# HC06_Schem.net
KiCad netlist of a schematic drawn in Altium Designer
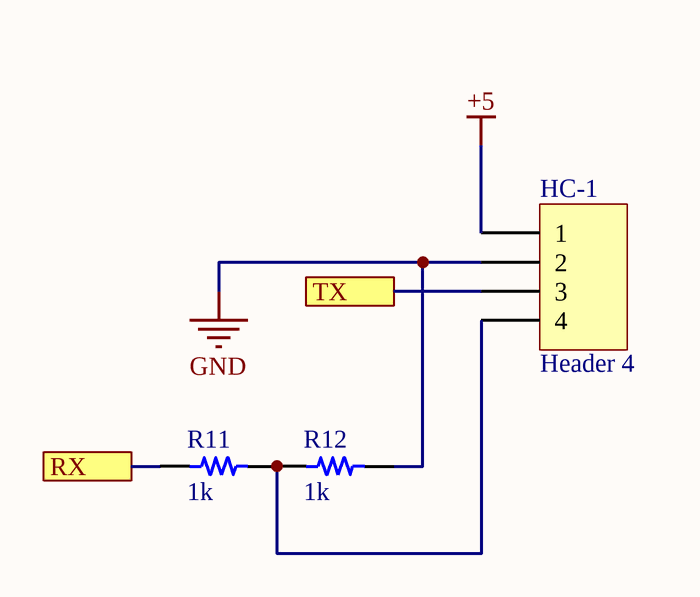
[diagram p0: HC06_Schem.SchDoc]

(export (version "E")
  (design (tool "Eeschema 10.0.6"))
  (components
    (comp (ref "HC-1")
      (value "Header 4")
      (footprint "HDR1X4")
      (description "Header, 4-Pin")
      (fields (field (name "PUBLISHER") "Altium Limited"))
      (libsource (lib "Miscellaneous Connectors") (part "Header 4"))
    )
    (comp (ref "R11")
      (value "1k")
      (footprint "RES 1206_3216")
      (description "RES SMD 10K OHM 1% 1/2W 1206")
      (fields (field (name "PART NUMBER") "ESR18EZPF1002") (field (name "MANUFACTURER") "Rohm Semiconductor"))
      (libsource (lib "Celestial Altium Library - altium_library") (part "Resistor"))
    )
    (comp (ref "R12")
      (value "1k")
      (footprint "RES 1206_3216")
      (description "RES SMD 10K OHM 1% 1/2W 1206")
      (fields (field (name "PART NUMBER") "ESR18EZPF1002") (field (name "MANUFACTURER") "Rohm Semiconductor"))
      (libsource (lib "Celestial Altium Library - altium_library") (part "Resistor"))
    )
  )
  (nets
    (net (code "1") (name "+5") (class "Default")
      (node (ref "HC-1") (pin "1") (pinfunction "1_1") (pintype "passive"))
    )
    (net (code "2") (name "/RX") (class "Default")
      (node (ref "R11") (pin "2") (pinfunction "2_2") (pintype "passive"))
    )
    (net (code "3") (name "/TX") (class "Default")
      (node (ref "HC-1") (pin "3") (pinfunction "3_3") (pintype "passive"))
    )
    (net (code "4") (name "GND") (class "Default")
      (node (ref "HC-1") (pin "2") (pinfunction "2_2") (pintype "passive"))
      (node (ref "R12") (pin "1") (pinfunction "1_1") (pintype "passive"))
    )
    (net (code "5") (name "Net-(HC-1-Pad4)") (class "Default")
      (node (ref "HC-1") (pin "4") (pinfunction "4_4") (pintype "passive"))
      (node (ref "R11") (pin "1") (pinfunction "1_1") (pintype "passive"))
      (node (ref "R12") (pin "2") (pinfunction "2_2") (pintype "passive"))
    )
  )
)
